# MCU_Module.net
KiCad netlist of a schematic drawn in Altium Designer
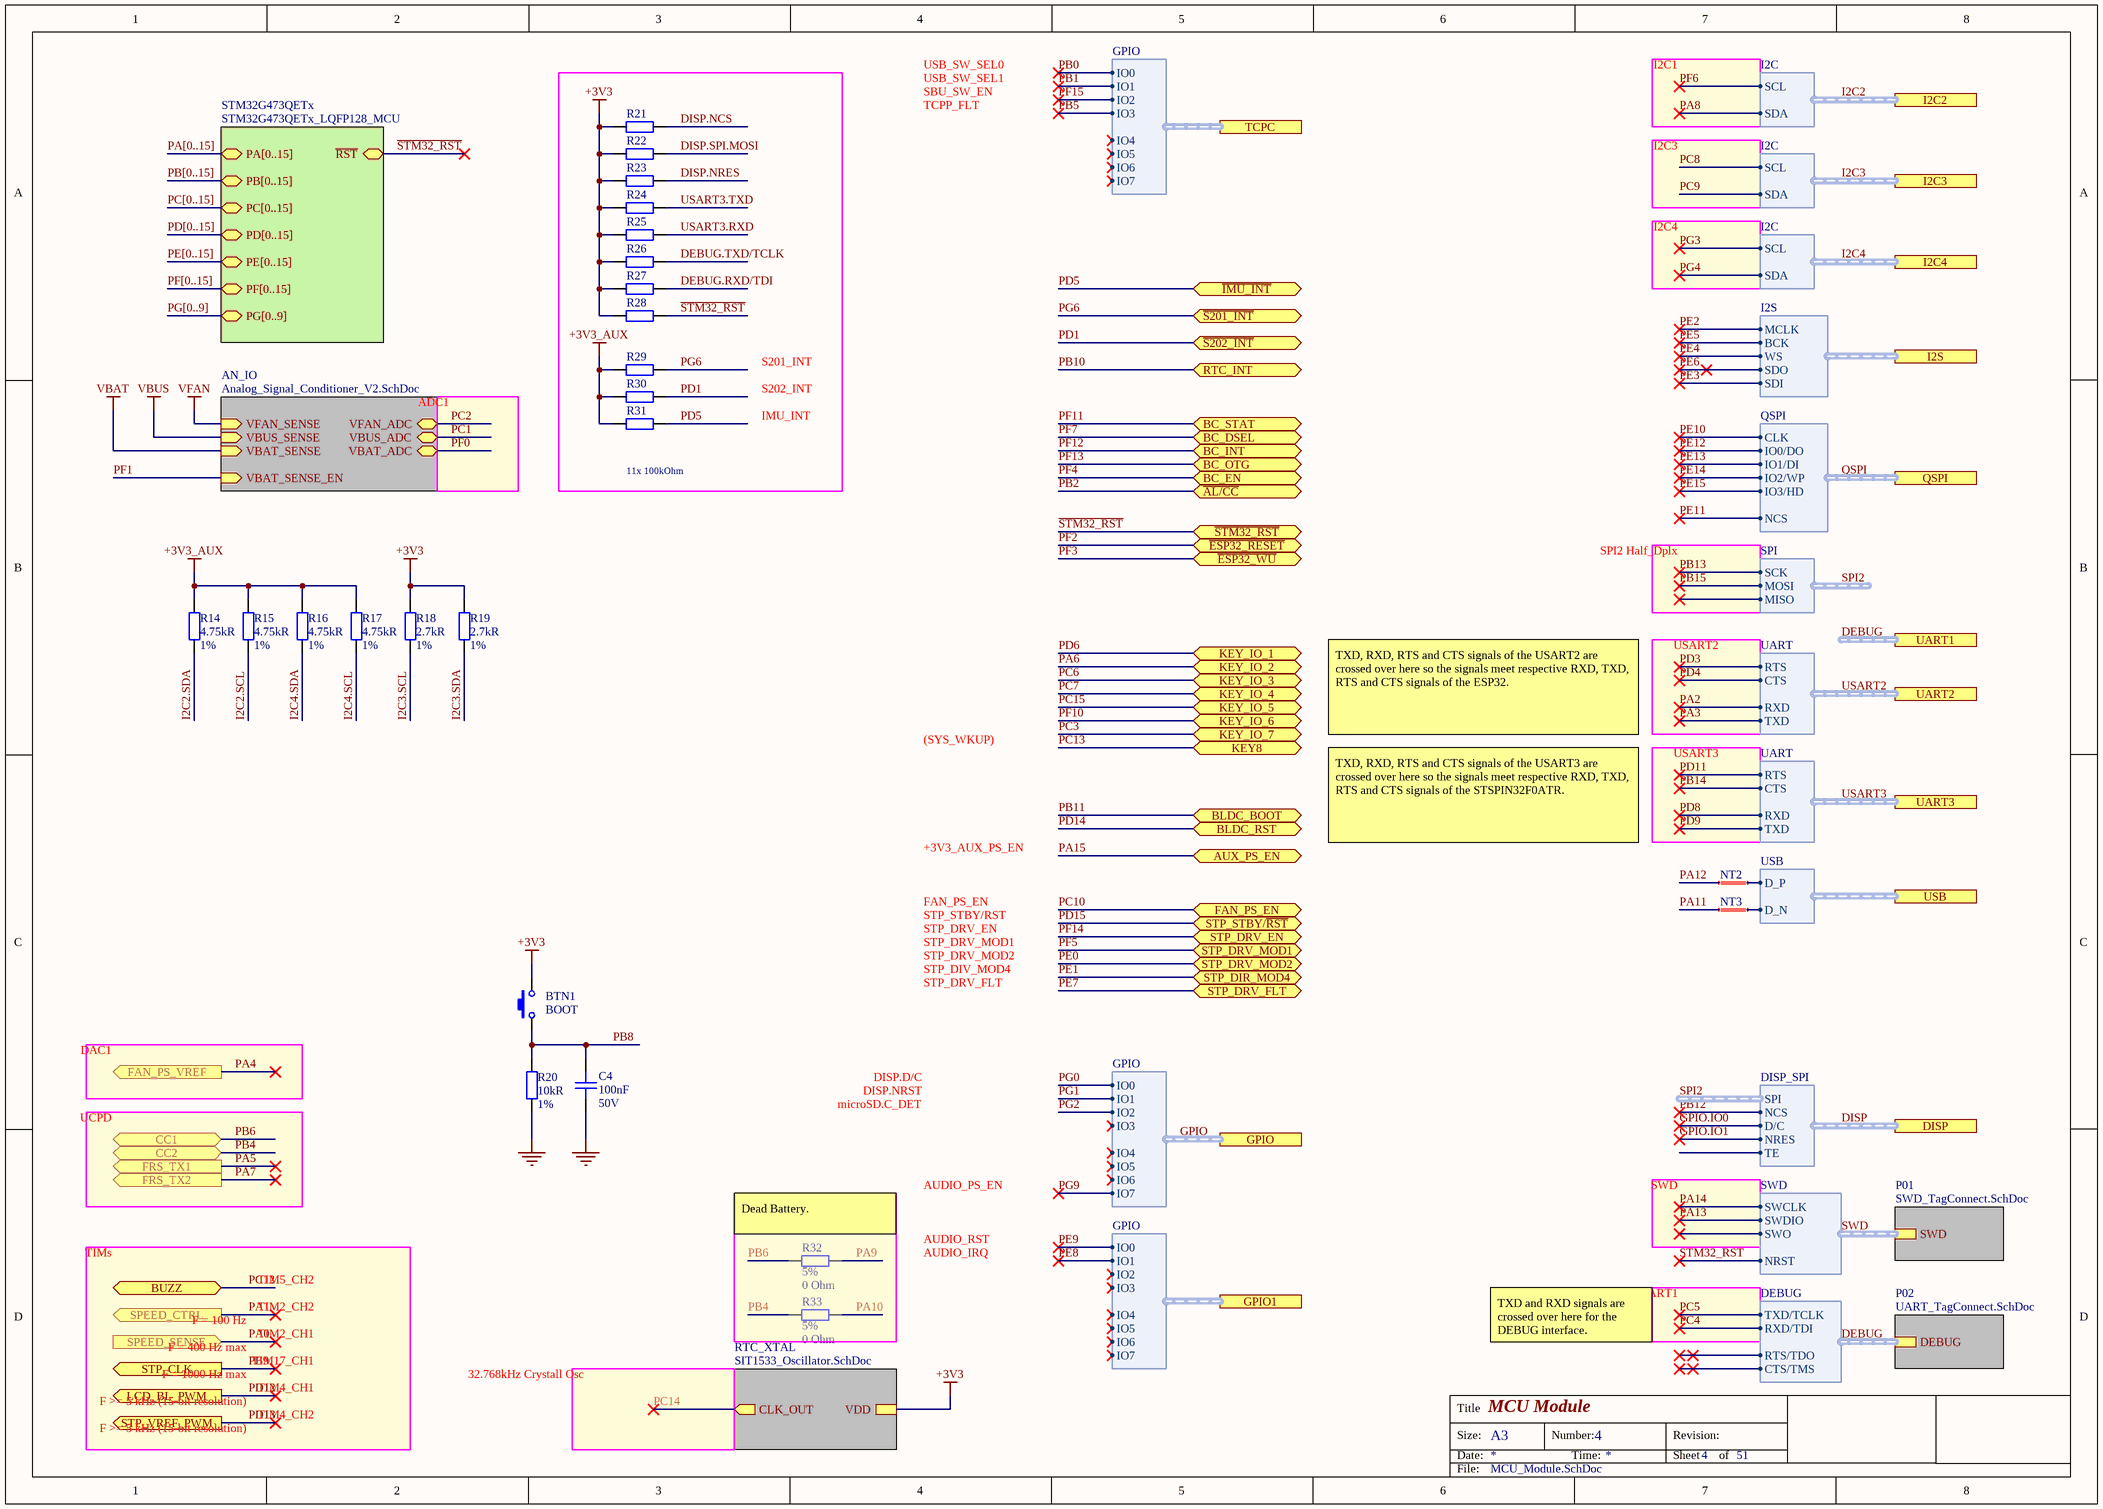
[diagram p0: MCU_Module.SchDoc]

(export (version "E")
  (design (tool "Eeschema 10.0.6"))
  (components
    (comp (ref "BTN1")
      (value "BOOT")
      (footprint "SWITCH USLPT2819DT2TR TACTILE TE")
      (description "Tactile Switch SPST-NO Top Actuated Surface Mount")
      (fields
        (field (name "MANUFACTURER") "TE Connectivity")
        (field (name "MANUFACTURER PART NUMBER") "USLPT2819DT2TR")
      )
      (libsource (lib "BLDC_Motor_Driver") (part "TACT ULTRA TB 2.8X1.9X0.6 160GF"))
    )
    (comp (ref "C4")
      (value "CAP CER 0.1UF 50V X7R 0402")
      (footprint "C0402")
      (description "0.1µF ±10% 50V Ceramic Capacitor X7R 0402 (1005 Metric)")
      (fields
        (field (name "MANUFACTURER") "TDK")
        (field (name "MANUFACTURER PART NUMBER") "CGA2B3X7R1H104K050BB")
        (field (name "CAPACITANCE") "100nF")
        (field (name "VOLTAGE") "50V")
      )
      (libsource (lib "capacitors_smd") (part "CAP CER 0.1UF 50V X7R 0402"))
    )
    (comp (ref "NT2")
      (value "Net Tie")
      (footprint "Net Tie 6x30mil")
      (libsource (lib "BLDC_Motor_Driver") (part "Net Tie Line"))
    )
    (comp (ref "NT3")
      (value "Net Tie")
      (footprint "Net Tie 6x30mil")
      (libsource (lib "BLDC_Motor_Driver") (part "Net Tie Line"))
    )
    (comp (ref "R14")
      (value "RES SMD 4.75K OHM 1% 1/16W 0402")
      (footprint "R0402")
      (description "4.75 kOhms ±1% 0.063W, 1/16W Chip Resistor 0402 (1005 Metric) Moisture Resistant Thick Film")
      (fields
        (field (name "MANUFACTURER") "Yageo")
        (field (name "MANUFACTURER PART NUMBER") "RC0402FR-074K75P")
        (field (name "RESISTANCE") "4.75kR")
        (field (name "TOLERANCE") "1%")
      )
      (libsource (lib "resistors_smd") (part "RES SMD 4.75K OHM 1% 1/16W 0402"))
    )
    (comp (ref "R15")
      (value "RES SMD 4.75K OHM 1% 1/16W 0402")
      (footprint "R0402")
      (description "4.75 kOhms ±1% 0.063W, 1/16W Chip Resistor 0402 (1005 Metric) Moisture Resistant Thick Film")
      (fields
        (field (name "MANUFACTURER") "Yageo")
        (field (name "MANUFACTURER PART NUMBER") "RC0402FR-074K75P")
        (field (name "RESISTANCE") "4.75kR")
        (field (name "TOLERANCE") "1%")
      )
      (libsource (lib "resistors_smd") (part "RES SMD 4.75K OHM 1% 1/16W 0402"))
    )
    (comp (ref "R16")
      (value "RES SMD 4.75K OHM 1% 1/16W 0402")
      (footprint "R0402")
      (description "4.75 kOhms ±1% 0.063W, 1/16W Chip Resistor 0402 (1005 Metric) Moisture Resistant Thick Film")
      (fields
        (field (name "MANUFACTURER") "Yageo")
        (field (name "MANUFACTURER PART NUMBER") "RC0402FR-074K75P")
        (field (name "RESISTANCE") "4.75kR")
        (field (name "TOLERANCE") "1%")
      )
      (libsource (lib "resistors_smd") (part "RES SMD 4.75K OHM 1% 1/16W 0402"))
    )
    (comp (ref "R17")
      (value "RES SMD 4.75K OHM 1% 1/16W 0402")
      (footprint "R0402")
      (description "4.75 kOhms ±1% 0.063W, 1/16W Chip Resistor 0402 (1005 Metric) Moisture Resistant Thick Film")
      (fields
        (field (name "MANUFACTURER") "Yageo")
        (field (name "MANUFACTURER PART NUMBER") "RC0402FR-074K75P")
        (field (name "RESISTANCE") "4.75kR")
        (field (name "TOLERANCE") "1%")
      )
      (libsource (lib "resistors_smd") (part "RES SMD 4.75K OHM 1% 1/16W 0402"))
    )
    (comp (ref "R18")
      (value "RES SMD 2.7K OHM 1% 1/16W 0402")
      (footprint "R0402")
      (description "2.7 kOhms ±1% 0.063W, 1/16W Chip Resistor 0402 (1005 Metric) Moisture Resistant Thick Film")
      (fields
        (field (name "MANUFACTURER") "Yageo")
        (field (name "MANUFACTURER PART NUMBER") "RC0402FR-072K7L")
        (field (name "RESISTANCE") "2.7kR")
        (field (name "TOLERANCE") "1%")
      )
      (libsource (lib "resistors_smd") (part "RES SMD 2.7K OHM 1% 1/16W 0402"))
    )
    (comp (ref "R19")
      (value "RES SMD 2.7K OHM 1% 1/16W 0402")
      (footprint "R0402")
      (description "2.7 kOhms ±1% 0.063W, 1/16W Chip Resistor 0402 (1005 Metric) Moisture Resistant Thick Film")
      (fields
        (field (name "MANUFACTURER") "Yageo")
        (field (name "MANUFACTURER PART NUMBER") "RC0402FR-072K7L")
        (field (name "RESISTANCE") "2.7kR")
        (field (name "TOLERANCE") "1%")
      )
      (libsource (lib "resistors_smd") (part "RES SMD 2.7K OHM 1% 1/16W 0402"))
    )
    (comp (ref "R20")
      (value "RES SMD 10K OHM 1% 1/16W 0402")
      (footprint "R0402")
      (description "10 kOhms ±1% 0.063W, 1/16W Chip Resistor 0402 (1005 Metric) Moisture Resistant Thick Film")
      (fields
        (field (name "MANUFACTURER PART NUMBER") "RC0402FR-0710KP")
        (field (name "MANUFACTURER") "Yageo")
        (field (name "RESISTANCE") "10kR")
        (field (name "TOLERANCE") "1%")
      )
      (libsource (lib "resistors_smd") (part "RES SMD 10K OHM 1% 1/16W 0402"))
    )
    (comp (ref "R21")
      (value "RES SMD 100K OHM 1% 1/16W 0402")
      (footprint "R0402")
      (description "100 kOhms ±1% 0.063W, 1/16W Chip Resistor 0402 (1005 Metric) Moisture Resistant Thick Film")
      (fields
        (field (name "MANUFACTURER") "Yageo")
        (field (name "MANUFACTURER PART NUMBER") "RC0402FR-07100KL")
      )
      (libsource (lib "resistors_smd") (part "RES SMD 100K OHM 1% 1/16W 0402"))
    )
    (comp (ref "R22")
      (value "RES SMD 100K OHM 1% 1/16W 0402")
      (footprint "R0402")
      (description "100 kOhms ±1% 0.063W, 1/16W Chip Resistor 0402 (1005 Metric) Moisture Resistant Thick Film")
      (fields
        (field (name "MANUFACTURER") "Yageo")
        (field (name "MANUFACTURER PART NUMBER") "RC0402FR-07100KL")
      )
      (libsource (lib "resistors_smd") (part "RES SMD 100K OHM 1% 1/16W 0402"))
    )
    (comp (ref "R23")
      (value "RES SMD 100K OHM 1% 1/16W 0402")
      (footprint "R0402")
      (description "100 kOhms ±1% 0.063W, 1/16W Chip Resistor 0402 (1005 Metric) Moisture Resistant Thick Film")
      (fields
        (field (name "MANUFACTURER") "Yageo")
        (field (name "MANUFACTURER PART NUMBER") "RC0402FR-07100KL")
      )
      (libsource (lib "resistors_smd") (part "RES SMD 100K OHM 1% 1/16W 0402"))
    )
    (comp (ref "R24")
      (value "RES SMD 100K OHM 1% 1/16W 0402")
      (footprint "R0402")
      (description "100 kOhms ±1% 0.063W, 1/16W Chip Resistor 0402 (1005 Metric) Moisture Resistant Thick Film")
      (fields
        (field (name "MANUFACTURER") "Yageo")
        (field (name "MANUFACTURER PART NUMBER") "RC0402FR-07100KL")
      )
      (libsource (lib "resistors_smd") (part "RES SMD 100K OHM 1% 1/16W 0402"))
    )
    (comp (ref "R25")
      (value "RES SMD 100K OHM 1% 1/16W 0402")
      (footprint "R0402")
      (description "100 kOhms ±1% 0.063W, 1/16W Chip Resistor 0402 (1005 Metric) Moisture Resistant Thick Film")
      (fields
        (field (name "MANUFACTURER") "Yageo")
        (field (name "MANUFACTURER PART NUMBER") "RC0402FR-07100KL")
      )
      (libsource (lib "resistors_smd") (part "RES SMD 100K OHM 1% 1/16W 0402"))
    )
    (comp (ref "R26")
      (value "RES SMD 100K OHM 1% 1/16W 0402")
      (footprint "R0402")
      (description "100 kOhms ±1% 0.063W, 1/16W Chip Resistor 0402 (1005 Metric) Moisture Resistant Thick Film")
      (fields
        (field (name "MANUFACTURER") "Yageo")
        (field (name "MANUFACTURER PART NUMBER") "RC0402FR-07100KL")
      )
      (libsource (lib "resistors_smd") (part "RES SMD 100K OHM 1% 1/16W 0402"))
    )
    (comp (ref "R27")
      (value "RES SMD 100K OHM 1% 1/16W 0402")
      (footprint "R0402")
      (description "100 kOhms ±1% 0.063W, 1/16W Chip Resistor 0402 (1005 Metric) Moisture Resistant Thick Film")
      (fields
        (field (name "MANUFACTURER") "Yageo")
        (field (name "MANUFACTURER PART NUMBER") "RC0402FR-07100KL")
      )
      (libsource (lib "resistors_smd") (part "RES SMD 100K OHM 1% 1/16W 0402"))
    )
    (comp (ref "R28")
      (value "RES SMD 100K OHM 1% 1/16W 0402")
      (footprint "R0402")
      (description "100 kOhms ±1% 0.063W, 1/16W Chip Resistor 0402 (1005 Metric) Moisture Resistant Thick Film")
      (fields
        (field (name "MANUFACTURER") "Yageo")
        (field (name "MANUFACTURER PART NUMBER") "RC0402FR-07100KL")
      )
      (libsource (lib "resistors_smd") (part "RES SMD 100K OHM 1% 1/16W 0402"))
    )
    (comp (ref "R29")
      (value "RES SMD 100K OHM 1% 1/16W 0402")
      (footprint "R0402")
      (description "100 kOhms ±1% 0.063W, 1/16W Chip Resistor 0402 (1005 Metric) Moisture Resistant Thick Film")
      (fields
        (field (name "MANUFACTURER") "Yageo")
        (field (name "MANUFACTURER PART NUMBER") "RC0402FR-07100KL")
      )
      (libsource (lib "resistors_smd") (part "RES SMD 100K OHM 1% 1/16W 0402"))
    )
    (comp (ref "R30")
      (value "RES SMD 100K OHM 1% 1/16W 0402")
      (footprint "R0402")
      (description "100 kOhms ±1% 0.063W, 1/16W Chip Resistor 0402 (1005 Metric) Moisture Resistant Thick Film")
      (fields
        (field (name "MANUFACTURER") "Yageo")
        (field (name "MANUFACTURER PART NUMBER") "RC0402FR-07100KL")
      )
      (libsource (lib "resistors_smd") (part "RES SMD 100K OHM 1% 1/16W 0402"))
    )
    (comp (ref "R31")
      (value "RES SMD 100K OHM 1% 1/16W 0402")
      (footprint "R0402")
      (description "100 kOhms ±1% 0.063W, 1/16W Chip Resistor 0402 (1005 Metric) Moisture Resistant Thick Film")
      (fields
        (field (name "MANUFACTURER") "Yageo")
        (field (name "MANUFACTURER PART NUMBER") "RC0402FR-07100KL")
      )
      (libsource (lib "resistors_smd") (part "RES SMD 100K OHM 1% 1/16W 0402"))
    )
    (comp (ref "R32")
      (value "RES SMD 0 OHM JUMPER 1/16W 0402")
      (footprint "R0402")
      (description "0 Ohms Jumper 0.063W, 1/16W Chip Resistor 0402 (1005 Metric) Moisture Resistant Thick Film")
      (fields
        (field (name "MANUFACTURER") "Yageo")
        (field (name "MANUFACTURER PART NUMBER") "RC0402JR-070RL")
        (field (name "TOLERANCE") "5%")
        (field (name "RESISTANCE") "0 Ohm")
      )
      (libsource (lib "resistors_smd") (part "RES SMD 0 OHM JUMPER 1/16W 0402"))
    )
    (comp (ref "R33")
      (value "RES SMD 0 OHM JUMPER 1/16W 0402")
      (footprint "R0402")
      (description "0 Ohms Jumper 0.063W, 1/16W Chip Resistor 0402 (1005 Metric) Moisture Resistant Thick Film")
      (fields
        (field (name "MANUFACTURER") "Yageo")
        (field (name "MANUFACTURER PART NUMBER") "RC0402JR-070RL")
        (field (name "TOLERANCE") "5%")
        (field (name "RESISTANCE") "0 Ohm")
      )
      (libsource (lib "resistors_smd") (part "RES SMD 0 OHM JUMPER 1/16W 0402"))
    )
  )
  (nets
    (net (code "30") (name "+3V3") (class "Default")
      (node (ref "BTN1") (pin "1") (pinfunction "1_1") (pintype "passive"))
      (node (ref "R18") (pin "2") (pinfunction "2_2") (pintype "passive"))
      (node (ref "R19") (pin "2") (pinfunction "2_2") (pintype "passive"))
      (node (ref "R21") (pin "1") (pinfunction "1_1") (pintype "passive"))
      (node (ref "R22") (pin "1") (pinfunction "1_1") (pintype "passive"))
      (node (ref "R23") (pin "1") (pinfunction "1_1") (pintype "passive"))
      (node (ref "R24") (pin "1") (pinfunction "1_1") (pintype "passive"))
      (node (ref "R25") (pin "1") (pinfunction "1_1") (pintype "passive"))
      (node (ref "R26") (pin "1") (pinfunction "1_1") (pintype "passive"))
      (node (ref "R27") (pin "1") (pinfunction "1_1") (pintype "passive"))
      (node (ref "R28") (pin "1") (pinfunction "1_1") (pintype "passive"))
    )
    (net (code "31") (name "+3V3_AUX") (class "Default")
      (node (ref "R14") (pin "2") (pinfunction "2_2") (pintype "passive"))
      (node (ref "R15") (pin "2") (pinfunction "2_2") (pintype "passive"))
      (node (ref "R16") (pin "2") (pinfunction "2_2") (pintype "passive"))
      (node (ref "R17") (pin "2") (pinfunction "2_2") (pintype "passive"))
      (node (ref "R29") (pin "1") (pinfunction "1_1") (pintype "passive"))
      (node (ref "R30") (pin "1") (pinfunction "1_1") (pintype "passive"))
      (node (ref "R31") (pin "1") (pinfunction "1_1") (pintype "passive"))
    )
    (net (code "33") (name "/DEBUG.RXD{slash}TDI") (class "Default")
      (node (ref "R27") (pin "2") (pinfunction "2_2") (pintype "passive"))
    )
    (net (code "34") (name "/DEBUG.TXD{slash}TCLK") (class "Default")
      (node (ref "R26") (pin "2") (pinfunction "2_2") (pintype "passive"))
    )
    (net (code "36") (name "/DISP.NCS") (class "Default")
      (node (ref "R21") (pin "2") (pinfunction "2_2") (pintype "passive"))
    )
    (net (code "37") (name "/DISP.NRES") (class "Default")
      (node (ref "R23") (pin "2") (pinfunction "2_2") (pintype "passive"))
    )
    (net (code "38") (name "/DISP.SPI.MOSI") (class "Default")
      (node (ref "R22") (pin "2") (pinfunction "2_2") (pintype "passive"))
    )
    (net (code "40") (name "/D_N") (class "Default") (node (ref "NT3") (pin "2") (pintype "passive")))
    (net (code "41") (name "/D_P") (class "Default") (node (ref "NT2") (pin "2") (pintype "passive")))
    (net (code "45") (name "/I2C2.SCL") (class "Default")
      (node (ref "R15") (pin "1") (pinfunction "1_1") (pintype "passive"))
    )
    (net (code "46") (name "/I2C2.SDA") (class "Default")
      (node (ref "R14") (pin "1") (pinfunction "1_1") (pintype "passive"))
    )
    (net (code "48") (name "/I2C3.SCL") (class "Default")
      (node (ref "R18") (pin "1") (pinfunction "1_1") (pintype "passive"))
    )
    (net (code "49") (name "/I2C3.SDA") (class "Default")
      (node (ref "R19") (pin "1") (pinfunction "1_1") (pintype "passive"))
    )
    (net (code "51") (name "/I2C4.SCL") (class "Default")
      (node (ref "R17") (pin "1") (pinfunction "1_1") (pintype "passive"))
    )
    (net (code "52") (name "/I2C4.SDA") (class "Default")
      (node (ref "R16") (pin "1") (pinfunction "1_1") (pintype "passive"))
    )
    (net (code "64") (name "/PA9") (class "Default")
      (node (ref "R32") (pin "2") (pinfunction "2_2") (pintype "passive"))
    )
    (net (code "65") (name "/PA10") (class "Default")
      (node (ref "R33") (pin "2") (pinfunction "2_2") (pintype "passive"))
    )
    (net (code "66") (name "/PA11") (class "Default") (node (ref "NT3") (pin "1") (pintype "passive")))
    (net (code "67") (name "/PA12") (class "Default") (node (ref "NT2") (pin "1") (pintype "passive")))
    (net (code "75") (name "/PB4") (class "Default")
      (node (ref "R33") (pin "1") (pinfunction "1_1") (pintype "passive"))
    )
    (net (code "77") (name "/PB6") (class "Default")
      (node (ref "R32") (pin "1") (pinfunction "1_1") (pintype "passive"))
    )
    (net (code "78") (name "/PB8") (class "Default")
      (node (ref "BTN1") (pin "2") (pinfunction "2_2") (pintype "passive"))
      (node (ref "C4") (pin "2") (pinfunction "2_2") (pintype "passive"))
      (node (ref "R20") (pin "1") (pinfunction "1_1") (pintype "passive"))
    )
    (net (code "102") (name "/PD1") (class "Default")
      (node (ref "R30") (pin "2") (pinfunction "2_2") (pintype "passive"))
    )
    (net (code "105") (name "/PD5") (class "Default")
      (node (ref "R31") (pin "2") (pinfunction "2_2") (pintype "passive"))
    )
    (net (code "152") (name "/PG6") (class "Default")
      (node (ref "R29") (pin "2") (pinfunction "2_2") (pintype "passive"))
    )
    (net (code "158") (name "/STM32_RST") (class "Default")
      (node (ref "R28") (pin "2") (pinfunction "2_2") (pintype "passive"))
    )
    (net (code "163") (name "/USART3.RXD") (class "Default")
      (node (ref "R25") (pin "2") (pinfunction "2_2") (pintype "passive"))
    )
    (net (code "164") (name "/USART3.TXD") (class "Default")
      (node (ref "R24") (pin "2") (pinfunction "2_2") (pintype "passive"))
    )
    (net (code "171") (name "GND") (class "Default")
      (node (ref "C4") (pin "1") (pinfunction "1_1") (pintype "passive"))
      (node (ref "R20") (pin "2") (pinfunction "2_2") (pintype "passive"))
    )
  )
)
